# RelayBoard.net
KiCad netlist of a schematic drawn in EAGLE
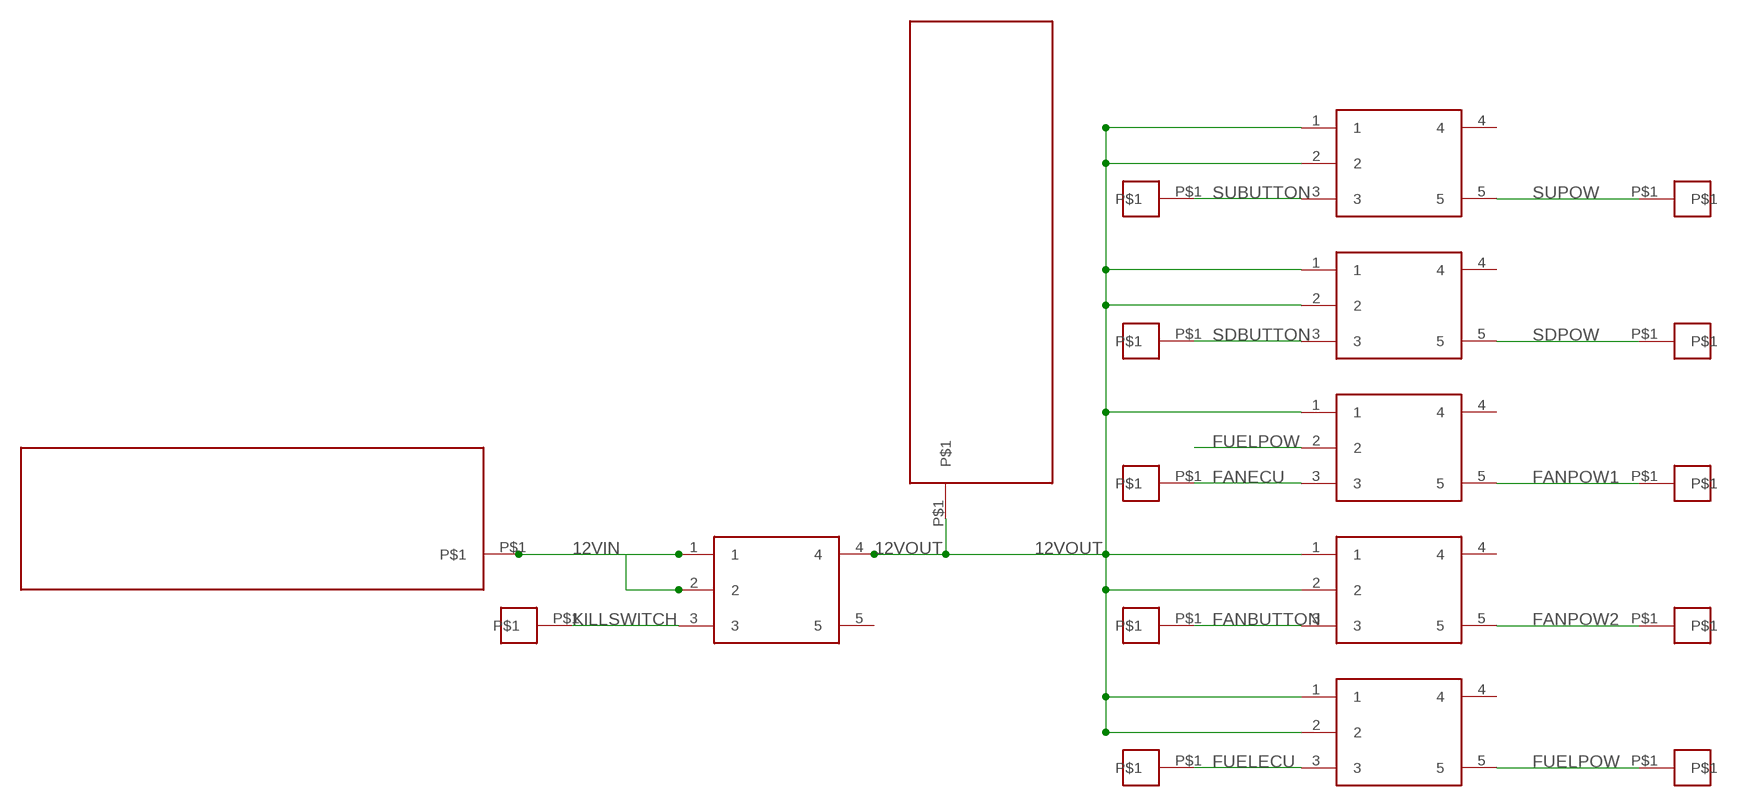
[diagram p0: schematic, sheet 1]

(export (version "E")
  (design (tool "Eeschema 10.0.6"))
  (components
    (comp (ref "U$1")
      (value "RELAY")
      (footprint "eagle-import:RELAY")
      (libsource (lib "eagle-import") (part "RELAY"))
    )
    (comp (ref "U$2")
      (value "RELAY")
      (footprint "eagle-import:RELAY")
      (libsource (lib "eagle-import") (part "RELAY"))
    )
    (comp (ref "U$3")
      (value "RELAY")
      (footprint "eagle-import:RELAY")
      (libsource (lib "eagle-import") (part "RELAY"))
    )
    (comp (ref "U$4")
      (value "RELAY")
      (footprint "eagle-import:RELAY")
      (libsource (lib "eagle-import") (part "RELAY"))
    )
    (comp (ref "U$5")
      (value "RELAY")
      (footprint "eagle-import:RELAY")
      (libsource (lib "eagle-import") (part "RELAY"))
    )
    (comp (ref "U$6")
      (value "RELAY")
      (footprint "eagle-import:RELAY")
      (libsource (lib "eagle-import") (part "RELAY"))
    )
    (comp (ref "U$7")
      (value "PLUG2")
      (footprint "eagle-import:PLUG2")
      (libsource (lib "eagle-import") (part "PLUG2"))
    )
    (comp (ref "U$8")
      (value "PLUG2")
      (footprint "eagle-import:PLUG2")
      (libsource (lib "eagle-import") (part "PLUG2"))
    )
    (comp (ref "U$9")
      (value "OUTPUT")
      (footprint "eagle-import:OUTPUT")
      (libsource (lib "eagle-import") (part "OUTPUT"))
    )
    (comp (ref "U$10")
      (value "OUTPUT")
      (footprint "eagle-import:OUTPUT")
      (libsource (lib "eagle-import") (part "OUTPUT"))
    )
    (comp (ref "U$11")
      (value "OUTPUT")
      (footprint "eagle-import:OUTPUT")
      (libsource (lib "eagle-import") (part "OUTPUT"))
    )
    (comp (ref "U$12")
      (value "OUTPUT")
      (footprint "eagle-import:OUTPUT")
      (libsource (lib "eagle-import") (part "OUTPUT"))
    )
    (comp (ref "U$13")
      (value "OUTPUT")
      (footprint "eagle-import:OUTPUT")
      (libsource (lib "eagle-import") (part "OUTPUT"))
    )
    (comp (ref "U$14")
      (value "OUTPUT")
      (footprint "eagle-import:OUTPUT")
      (libsource (lib "eagle-import") (part "OUTPUT"))
    )
    (comp (ref "U$15")
      (value "OUTPUT")
      (footprint "eagle-import:OUTPUT")
      (libsource (lib "eagle-import") (part "OUTPUT"))
    )
    (comp (ref "U$16")
      (value "OUTPUT")
      (footprint "eagle-import:OUTPUT")
      (libsource (lib "eagle-import") (part "OUTPUT"))
    )
    (comp (ref "U$17")
      (value "OUTPUT")
      (footprint "eagle-import:OUTPUT")
      (libsource (lib "eagle-import") (part "OUTPUT"))
    )
    (comp (ref "U$18")
      (value "OUTPUT")
      (footprint "eagle-import:OUTPUT")
      (libsource (lib "eagle-import") (part "OUTPUT"))
    )
    (comp (ref "U$19")
      (value "OUTPUT")
      (footprint "eagle-import:OUTPUT")
      (libsource (lib "eagle-import") (part "OUTPUT"))
    )
  )
  (nets
    (net (code "1") (name "/12VIN") (class "Default")
      (node (ref "U$6") (pin "1") (pinfunction "1_1") (pintype "bidirectional"))
      (node (ref "U$6") (pin "2") (pinfunction "2_2") (pintype "bidirectional"))
      (node (ref "U$7") (pin "P$1") (pinfunction "P$1_P$1") (pintype "bidirectional"))
    )
    (net (code "2") (name "/12VOUT") (class "Default")
      (node (ref "U$1") (pin "1") (pinfunction "1_1") (pintype "bidirectional"))
      (node (ref "U$1") (pin "2") (pinfunction "2_2") (pintype "bidirectional"))
      (node (ref "U$2") (pin "1") (pinfunction "1_1") (pintype "bidirectional"))
      (node (ref "U$2") (pin "2") (pinfunction "2_2") (pintype "bidirectional"))
      (node (ref "U$3") (pin "1") (pinfunction "1_1") (pintype "bidirectional"))
      (node (ref "U$4") (pin "1") (pinfunction "1_1") (pintype "bidirectional"))
      (node (ref "U$4") (pin "2") (pinfunction "2_2") (pintype "bidirectional"))
      (node (ref "U$5") (pin "1") (pinfunction "1_1") (pintype "bidirectional"))
      (node (ref "U$5") (pin "2") (pinfunction "2_2") (pintype "bidirectional"))
      (node (ref "U$6") (pin "4") (pinfunction "4_4") (pintype "bidirectional"))
      (node (ref "U$8") (pin "P$1") (pinfunction "P$1_P$1") (pintype "bidirectional"))
    )
    (net (code "3") (name "/FANBUTTON") (class "Default")
      (node (ref "U$11") (pin "P$1") (pinfunction "P$1_P$1") (pintype "bidirectional"))
      (node (ref "U$4") (pin "3") (pinfunction "3_3") (pintype "bidirectional"))
    )
    (net (code "4") (name "/FANECU") (class "Default")
      (node (ref "U$10") (pin "P$1") (pinfunction "P$1_P$1") (pintype "bidirectional"))
      (node (ref "U$3") (pin "3") (pinfunction "3_3") (pintype "bidirectional"))
    )
    (net (code "5") (name "/FANPOW1") (class "Default")
      (node (ref "U$16") (pin "P$1") (pinfunction "P$1_P$1") (pintype "bidirectional"))
      (node (ref "U$3") (pin "5") (pinfunction "5_5") (pintype "bidirectional"))
    )
    (net (code "6") (name "/FANPOW2") (class "Default")
      (node (ref "U$17") (pin "P$1") (pinfunction "P$1_P$1") (pintype "bidirectional"))
      (node (ref "U$4") (pin "5") (pinfunction "5_5") (pintype "bidirectional"))
    )
    (net (code "7") (name "/FUELECU") (class "Default")
      (node (ref "U$12") (pin "P$1") (pinfunction "P$1_P$1") (pintype "bidirectional"))
      (node (ref "U$5") (pin "3") (pinfunction "3_3") (pintype "bidirectional"))
    )
    (net (code "8") (name "/FUELPOW") (class "Default")
      (node (ref "U$18") (pin "P$1") (pinfunction "P$1_P$1") (pintype "bidirectional"))
      (node (ref "U$3") (pin "2") (pinfunction "2_2") (pintype "bidirectional"))
      (node (ref "U$5") (pin "5") (pinfunction "5_5") (pintype "bidirectional"))
    )
    (net (code "9") (name "/KILLSWITCH") (class "Default")
      (node (ref "U$19") (pin "P$1") (pinfunction "P$1_P$1") (pintype "bidirectional"))
      (node (ref "U$6") (pin "3") (pinfunction "3_3") (pintype "bidirectional"))
    )
    (net (code "10") (name "/SDBUTTON") (class "Default")
      (node (ref "U$2") (pin "3") (pinfunction "3_3") (pintype "bidirectional"))
      (node (ref "U$9") (pin "P$1") (pinfunction "P$1_P$1") (pintype "bidirectional"))
    )
    (net (code "11") (name "/SDPOW") (class "Default")
      (node (ref "U$15") (pin "P$1") (pinfunction "P$1_P$1") (pintype "bidirectional"))
      (node (ref "U$2") (pin "5") (pinfunction "5_5") (pintype "bidirectional"))
    )
    (net (code "12") (name "/SUBUTTON") (class "Default")
      (node (ref "U$1") (pin "3") (pinfunction "3_3") (pintype "bidirectional"))
      (node (ref "U$13") (pin "P$1") (pinfunction "P$1_P$1") (pintype "bidirectional"))
    )
    (net (code "13") (name "/SUPOW") (class "Default")
      (node (ref "U$1") (pin "5") (pinfunction "5_5") (pintype "bidirectional"))
      (node (ref "U$14") (pin "P$1") (pinfunction "P$1_P$1") (pintype "bidirectional"))
    )
    (net (code "14") (name "unconnected-(U$1-Pad4)") (class "Default")
      (node (ref "U$1") (pin "4") (pinfunction "4_4") (pintype "bidirectional"))
    )
    (net (code "15") (name "unconnected-(U$2-Pad4)") (class "Default")
      (node (ref "U$2") (pin "4") (pinfunction "4_4") (pintype "bidirectional"))
    )
    (net (code "16") (name "unconnected-(U$3-Pad4)") (class "Default")
      (node (ref "U$3") (pin "4") (pinfunction "4_4") (pintype "bidirectional"))
    )
    (net (code "17") (name "unconnected-(U$4-Pad4)") (class "Default")
      (node (ref "U$4") (pin "4") (pinfunction "4_4") (pintype "bidirectional"))
    )
    (net (code "18") (name "unconnected-(U$5-Pad4)") (class "Default")
      (node (ref "U$5") (pin "4") (pinfunction "4_4") (pintype "bidirectional"))
    )
    (net (code "19") (name "unconnected-(U$6-Pad5)") (class "Default")
      (node (ref "U$6") (pin "5") (pinfunction "5_5") (pintype "bidirectional"))
    )
  )
)
